# CHANGE_FMU3_REV_C.net
KiCad netlist of a schematic drawn in Altium Designer
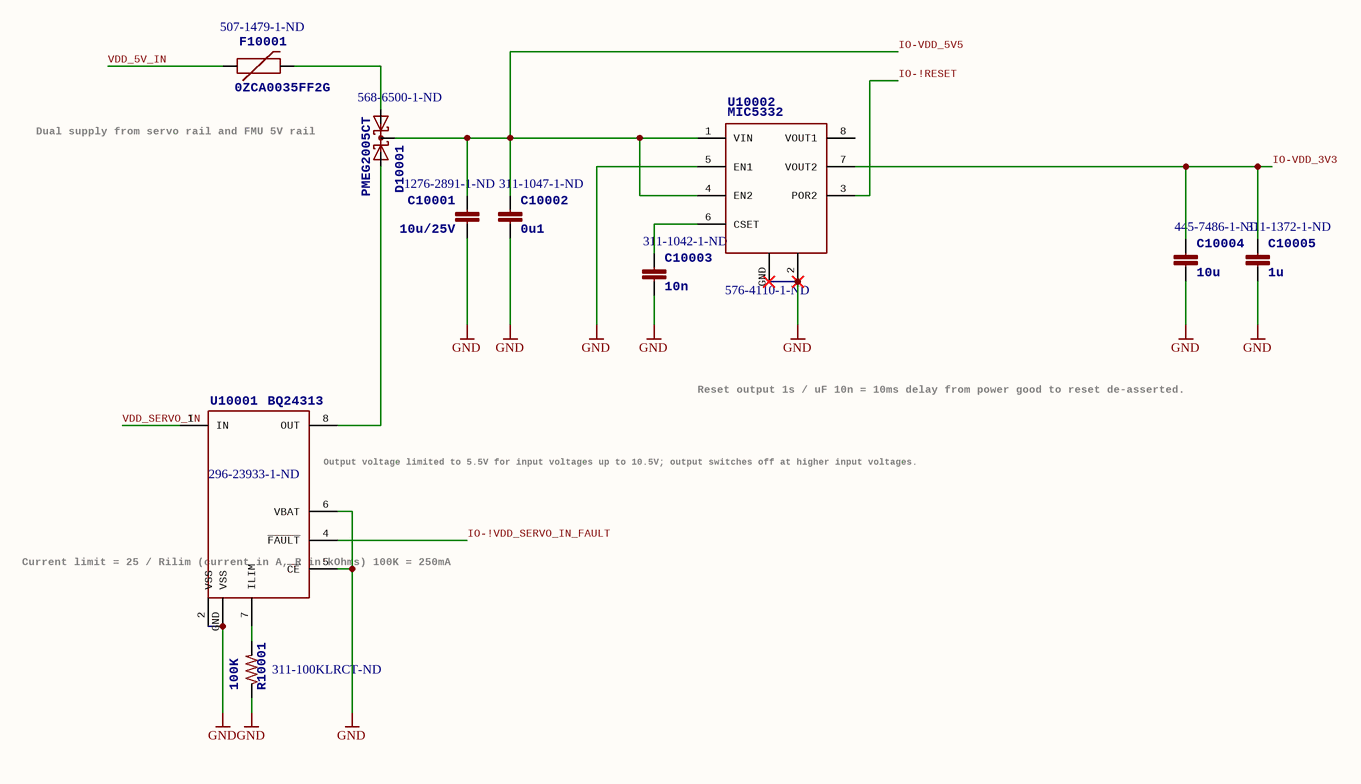
[diagram p0: CHANGE_FMU3_REV_C.SchDoc]

(export (version "E")
  (design (tool "Eeschema 10.0.6"))
  (components
    (comp (ref "C10001")
      (value "10u/25V")
      (footprint "0805-CAP")
      (description "CAP CER 10UF 25V 10% X5R 0805")
      (fields
        (field (name "PARTNO") "CL21A106KAYNNNE")
        (field (name "SUPPLIER PART NUMBER 1") "1276-2891-1-ND")
        (field (name "3DR_PARTNO") "ECM0714")
      )
      (libsource (lib "pixhawk2") (part "CAP0805"))
    )
    (comp (ref "C10002")
      (value "0u1")
      (footprint "0402-CAP")
      (description "CAP CER 0.1UF 16V Y5V 0402")
      (fields
        (field (name "PARTNO") "CC0402ZRY5V7BB104")
        (field (name "SUPPLIER PART NUMBER 1") "311-1047-1-ND")
        (field (name "3DR_PARTNO") "ECM0700")
      )
      (libsource (lib "pixhawk2") (part "CAP0402"))
    )
    (comp (ref "C10003")
      (value "10n")
      (footprint "0402-CAP")
      (description "CAP CER 10000PF 16V 10% X7R 0402")
      (fields
        (field (name "PARTNO") "CC0402KRX7R7BB103")
        (field (name "SUPPLIER PART NUMBER 1") "311-1042-1-ND")
        (field (name "3DR_PARTNO") "ECM0711")
      )
      (libsource (lib "pixhawk2") (part "CAP0402"))
    )
    (comp (ref "C10004")
      (value "10u")
      (footprint "0603-CAP")
      (description "CAP CER 10UF 10V 10% X5R 0603")
      (fields
        (field (name "PARTNO") "C1608X5R1A106K080AC")
        (field (name "SUPPLIER PART NUMBER 1") "445-7486-1-ND")
        (field (name "3DR_PARTNO") "ECM0712")
      )
      (libsource (lib "pixhawk2") (part "CAP0603"))
    )
    (comp (ref "C10005")
      (value "1u")
      (footprint "0603-CAP")
      (description "CAP CER 1UF 16V Y5V 0603")
      (fields
        (field (name "PARTNO") "CC0603ZRY5V7BB105")
        (field (name "SUPPLIER PART NUMBER 1") "311-1372-1-ND")
        (field (name "3DR_PARTNO") "ECM0705")
      )
      (libsource (lib "pixhawk2") (part "CAP0603"))
    )
    (comp (ref "D10001")
      (value "PMEG2005CT")
      (footprint "SOT23-3")
      (description "DIODE SCHOTTKY 20V 500MA TO236AB")
      (fields (field (name "SUPPLIER PART NUMBER 1") "568-6500-1-ND") (field (name "3DR_PARTNO") "ECM0838"))
      (libsource (lib "pixhawk2") (part "PMEG2005CT"))
    )
    (comp (ref "F10001")
      (value "0ZCA0035FF2G")
      (footprint "PTC-1206")
      (description "PTC RESTTBLE 0.35A 16V CHIP 1206")
      (fields (field (name "SUPPLIER PART NUMBER 1") "507-1479-1-ND") (field (name "3DR_PARTNO") "ECM0802"))
      (libsource (lib "pixhawk2") (part "PTCSMD"))
    )
    (comp (ref "R10001")
      (value "100K")
      (footprint "0402-RES")
      (description "RES 100K OHM 1/16W 1% 0402 SMD")
      (fields
        (field (name "SUPPLIER PART NUMBER 1") "311-100KLRCT-ND")
        (field (name "3DR_PARTNO") "ECM0818")
        (field (name "PARTNO") "RC0402FR-07100KL")
      )
      (libsource (lib "pixhawk2") (part "RESISTOR0402-RES"))
    )
    (comp (ref "U10001")
      (value "BQ24313")
      (footprint "QFN8-DSG")
      (description "IC LI+ CHARGER FRONT END 8-SON")
      (fields
        (field (name "SUPPLIER PART NUMBER 1") "296-23933-1-ND")
        (field (name "3DR_PARTNO") "ECM0824")
        (field (name "PARTNO") "BQ24313DSGT")
      )
      (libsource (lib "pixhawk2") (part "BQ24313"))
    )
    (comp (ref "U10002")
      (value "MIC5332")
      (footprint "MLF-8-EPAD")
      (description "IC REG LDO 3.3V 0.3A 8TMLF")
      (fields
        (field (name "SUPPLIER PART NUMBER 1") "576-4110-1-ND")
        (field (name "3DR_PARTNO") "ECM0832")
        (field (name "PARTNO") "MIC5332-SSYMT TR")
      )
      (libsource (lib "pixhawk2") (part "MIC5332"))
    )
  )
  (nets
    (net (code "1") (name "/IO-!RESET") (class "Default")
      (node (ref "U10002") (pin "3") (pinfunction "POR2_3") (pintype "passive"))
    )
    (net (code "2") (name "/IO-!VDD_SERVO_IN_FAULT") (class "Default")
      (node (ref "U10001") (pin "4") (pinfunction "~{FAULT}_4") (pintype "passive"))
    )
    (net (code "3") (name "/IO-VDD_3V3") (class "Default")
      (node (ref "C10004") (pin "P$1") (pinfunction "1_P$1") (pintype "passive"))
      (node (ref "C10005") (pin "P$1") (pinfunction "1_P$1") (pintype "passive"))
      (node (ref "U10002") (pin "7") (pinfunction "VOUT2_7") (pintype "passive"))
    )
    (net (code "4") (name "/IO-VDD_5V5") (class "Default")
      (node (ref "C10001") (pin "P$1") (pinfunction "1_P$1") (pintype "passive"))
      (node (ref "C10002") (pin "P$1") (pinfunction "1_P$1") (pintype "passive"))
      (node (ref "D10001") (pin "3") (pinfunction "CC_3") (pintype "passive"))
      (node (ref "U10002") (pin "1") (pinfunction "VIN_1") (pintype "passive"))
      (node (ref "U10002") (pin "4") (pinfunction "EN2_4") (pintype "passive"))
    )
    (net (code "5") (name "/VDD_5V_IN") (class "Default")
      (node (ref "F10001") (pin "1") (pinfunction "1_1") (pintype "passive"))
    )
    (net (code "6") (name "/VDD_SERVO_IN") (class "Default")
      (node (ref "U10001") (pin "1") (pinfunction "IN_1") (pintype "passive"))
    )
    (net (code "7") (name "GND") (class "Default")
      (node (ref "C10001") (pin "P$2") (pinfunction "2_P$2") (pintype "passive"))
      (node (ref "C10002") (pin "P$2") (pinfunction "2_P$2") (pintype "passive"))
      (node (ref "C10003") (pin "P$2") (pinfunction "2_P$2") (pintype "passive"))
      (node (ref "C10004") (pin "P$2") (pinfunction "2_P$2") (pintype "passive"))
      (node (ref "C10005") (pin "P$2") (pinfunction "2_P$2") (pintype "passive"))
      (node (ref "R10001") (pin "P$1") (pinfunction "1_P$1") (pintype "passive"))
      (node (ref "U10001") (pin "2") (pinfunction "VSS_2") (pintype "passive"))
      (node (ref "U10001") (pin "5") (pinfunction "~{CE}_5") (pintype "passive"))
      (node (ref "U10001") (pin "6") (pinfunction "VBAT_6") (pintype "passive"))
      (node (ref "U10001") (pin "GND") (pinfunction "VSS_GND") (pintype "passive"))
      (node (ref "U10002") (pin "2") (pinfunction "GND_2") (pintype "power_in"))
      (node (ref "U10002") (pin "5") (pinfunction "EN1_5") (pintype "passive"))
      (node (ref "U10002") (pin "GND") (pinfunction "GND_GND") (pintype "power_in"))
    )
    (net (code "8") (name "Net-(C10003-1)") (class "Default")
      (node (ref "C10003") (pin "P$1") (pinfunction "1_P$1") (pintype "passive"))
      (node (ref "U10002") (pin "6") (pinfunction "CSET_6") (pintype "passive"))
    )
    (net (code "9") (name "Net-(D10001-A1)") (class "Default")
      (node (ref "D10001") (pin "1") (pinfunction "A1_1") (pintype "passive"))
      (node (ref "F10001") (pin "2") (pinfunction "2_2") (pintype "passive"))
    )
    (net (code "10") (name "Net-(D10001-A2)") (class "Default")
      (node (ref "D10001") (pin "2") (pinfunction "A2_2") (pintype "passive"))
      (node (ref "U10001") (pin "8") (pinfunction "OUT_8") (pintype "passive"))
    )
    (net (code "11") (name "Net-(R10001-2)") (class "Default")
      (node (ref "R10001") (pin "P$2") (pinfunction "2_P$2") (pintype "passive"))
      (node (ref "U10001") (pin "7") (pinfunction "ILIM_7") (pintype "passive"))
    )
    (net (code "12") (name "unconnected-(U10002-VOUT1-Pad8)") (class "Default")
      (node (ref "U10002") (pin "8") (pinfunction "VOUT1_8") (pintype "passive"))
    )
  )
)
